# FPV_GROUND_STATION_SOURCE_FILE_PCB.net
KiCad netlist of a schematic drawn in EasyEDA Pro
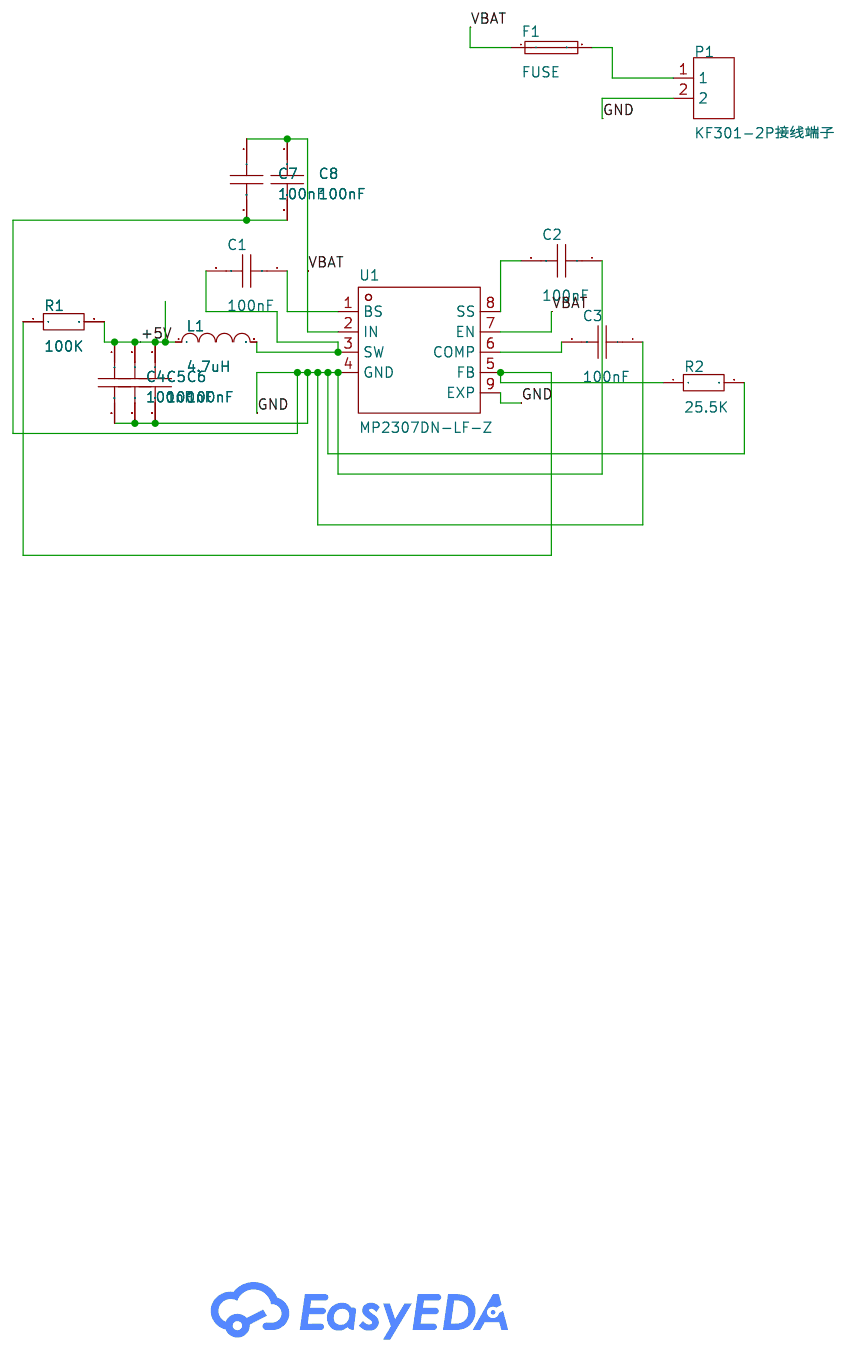
[diagram p0: POWER_BLK]
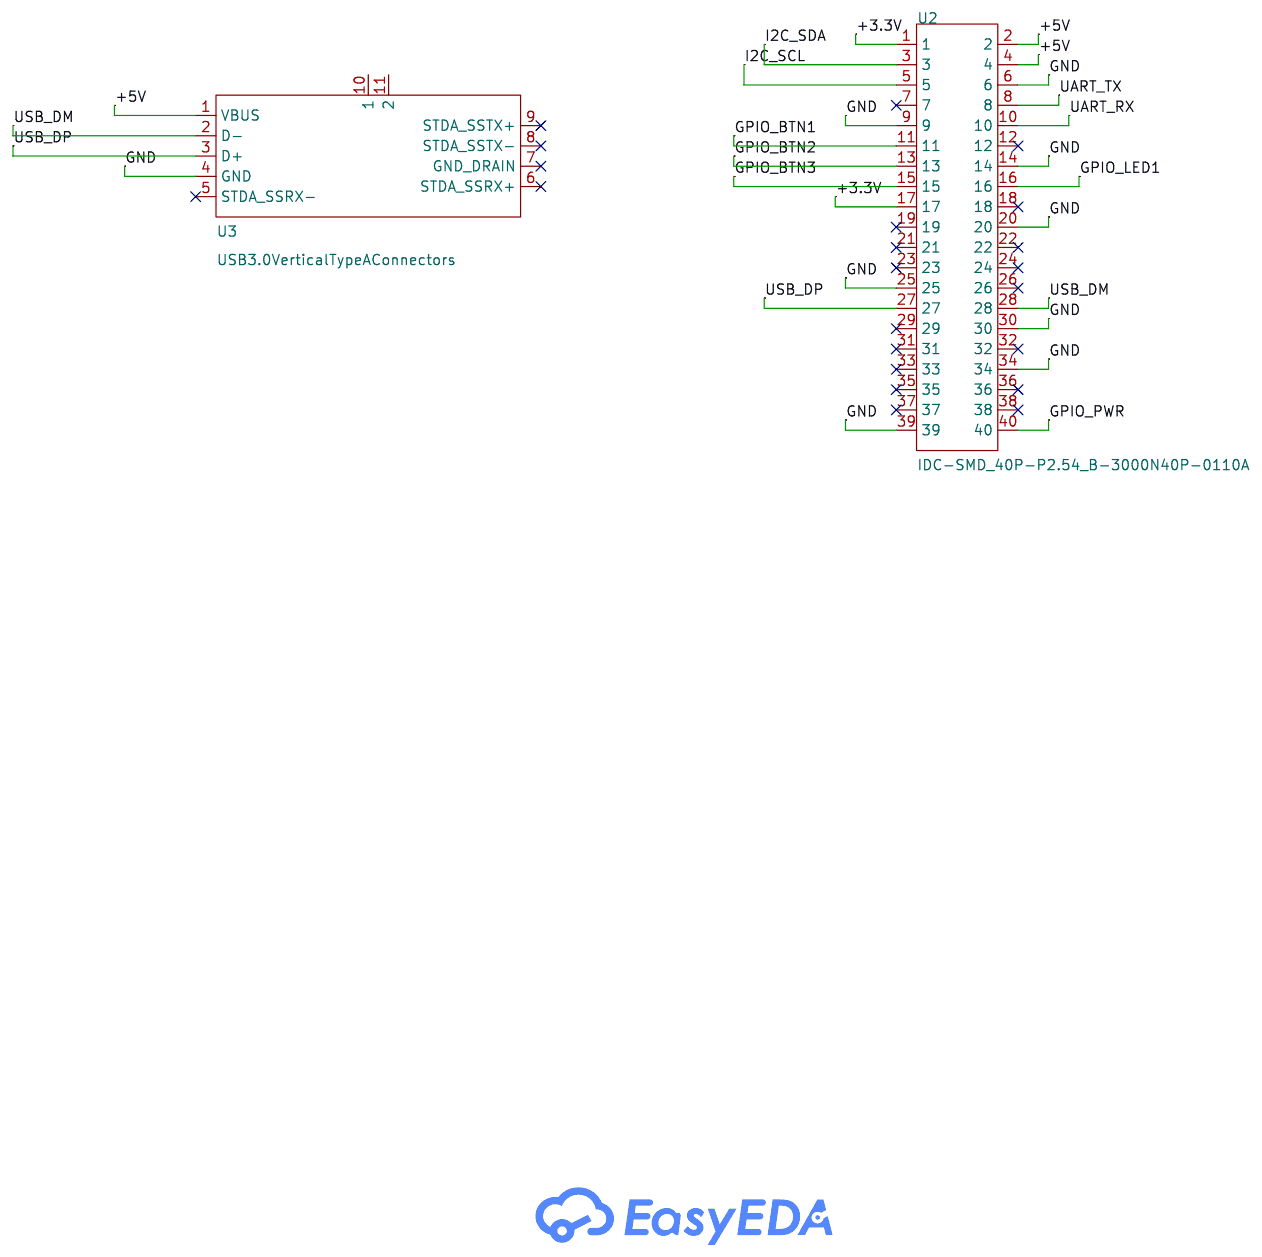
[diagram p1: GPIO header + USB-A]
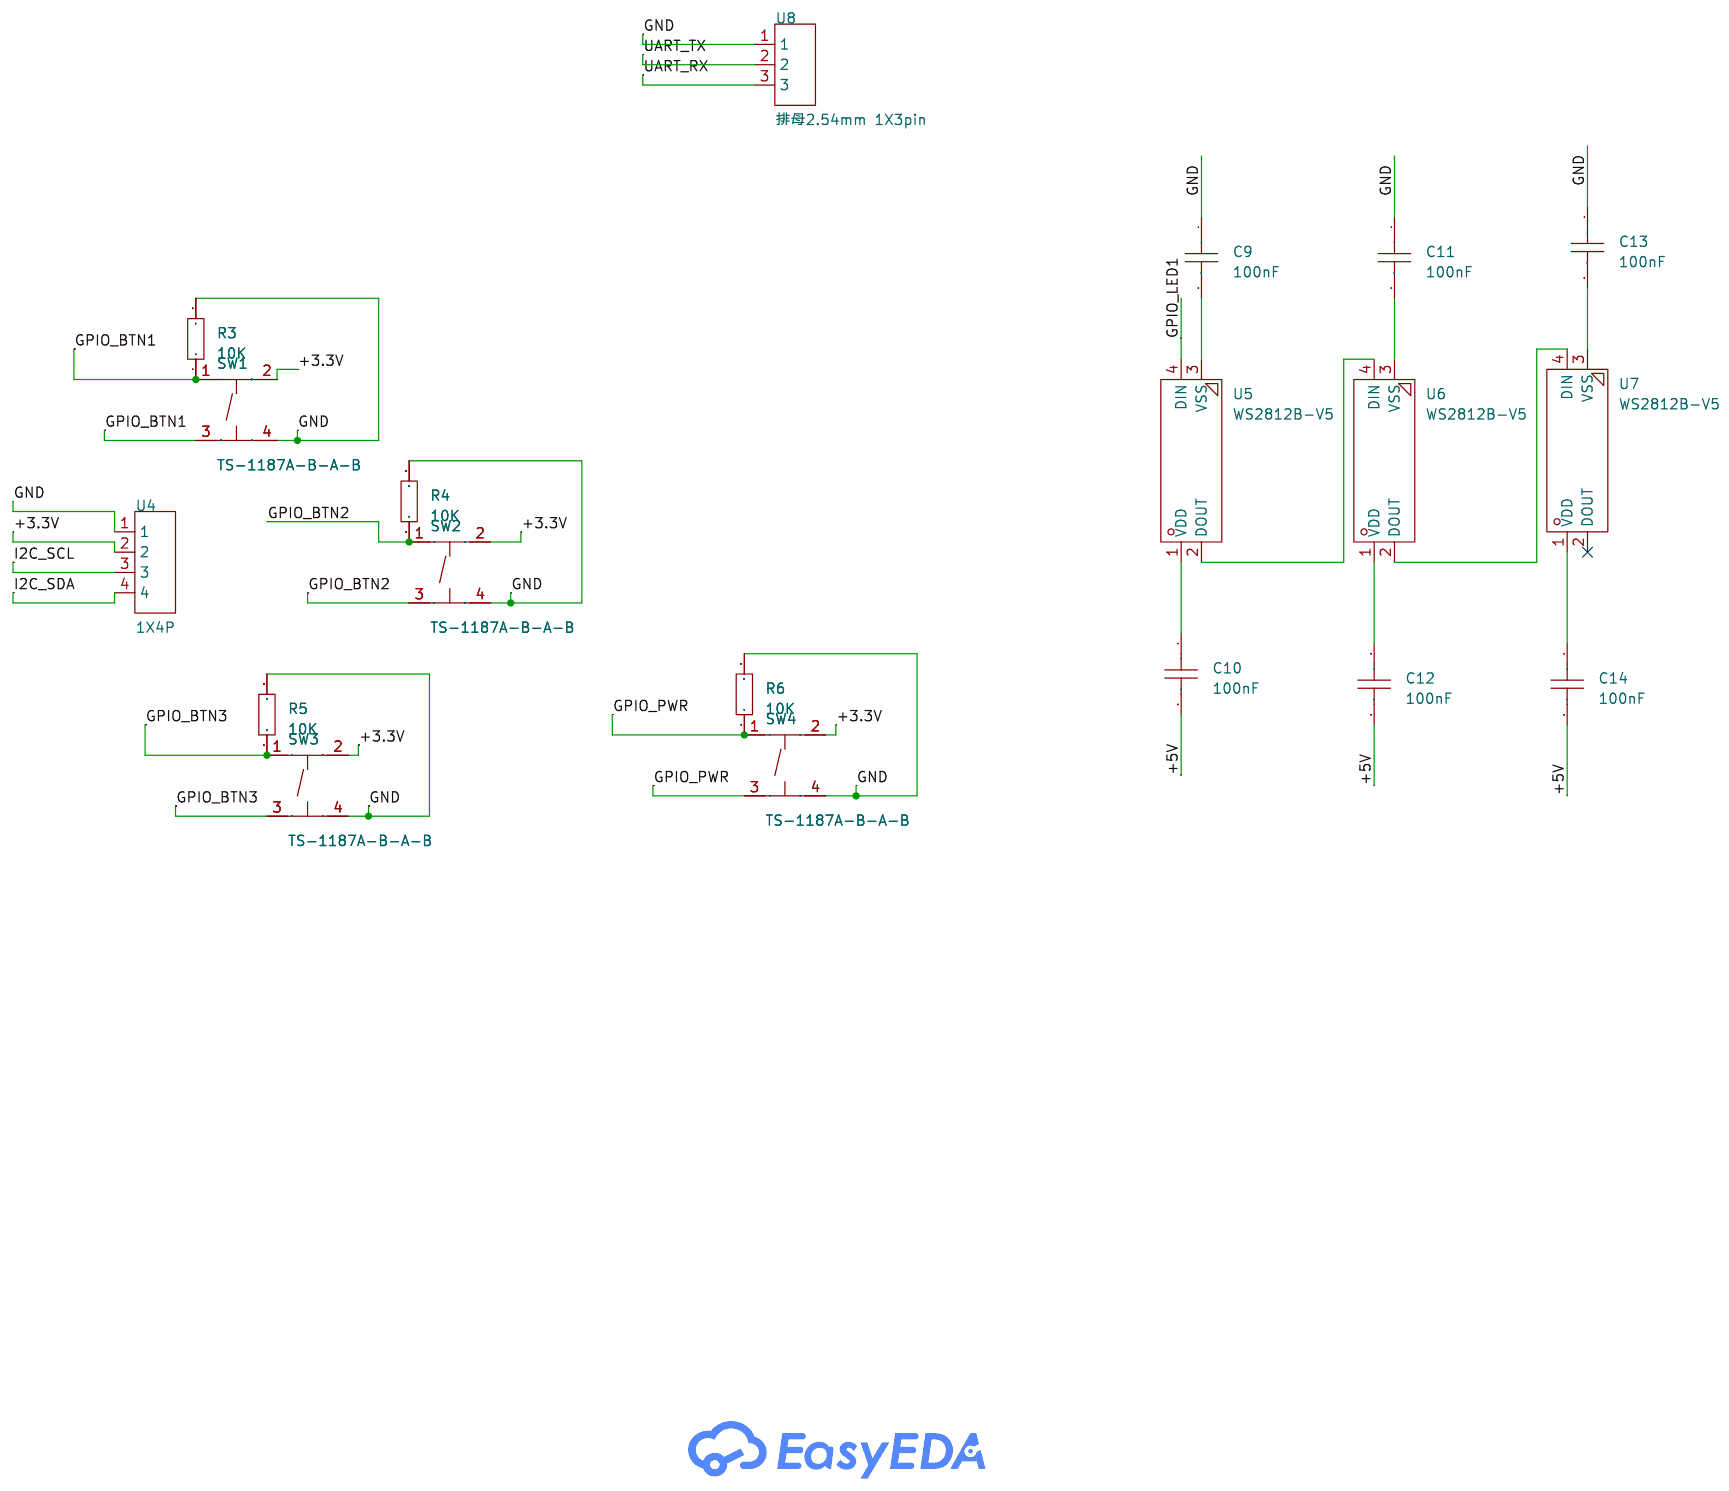
[diagram p2: LEDS AND OLED DISP]

(export (version "E")
  (design (tool "Eeschema 10.0.6"))
  (components
    (comp (ref "C1")
      (value "100nF")
      (footprint "easyedapro:C0603")
      (libsource (lib "easyedapro") (part "CAP"))
    )
    (comp (ref "C2")
      (value "100nF")
      (footprint "easyedapro:C0603")
      (libsource (lib "easyedapro") (part "CAP"))
    )
    (comp (ref "C3")
      (value "100nF")
      (footprint "easyedapro:C0603")
      (libsource (lib "easyedapro") (part "CAP"))
    )
    (comp (ref "C4")
      (value "100nF")
      (footprint "easyedapro:C0603")
      (libsource (lib "easyedapro") (part "CAP"))
    )
    (comp (ref "C5")
      (value "100nF")
      (footprint "easyedapro:C0603")
      (libsource (lib "easyedapro") (part "CAP"))
    )
    (comp (ref "C6")
      (value "100nF")
      (footprint "easyedapro:C0603")
      (libsource (lib "easyedapro") (part "CAP"))
    )
    (comp (ref "C7")
      (value "100nF")
      (footprint "easyedapro:C0603")
      (libsource (lib "easyedapro") (part "CAP"))
    )
    (comp (ref "C8")
      (value "100nF")
      (footprint "easyedapro:C0603")
      (libsource (lib "easyedapro") (part "CAP"))
    )
    (comp (ref "F1")
      (value "FUSE")
      (footprint "easyedapro:F1206")
      (libsource (lib "easyedapro") (part "FUSE"))
    )
    (comp (ref "L1")
      (value "4.7uH")
      (footprint "easyedapro:L0603")
      (libsource (lib "easyedapro") (part "电感"))
    )
    (comp (ref "P1")
      (value "KF301-2P接线端子")
      (footprint "easyedapro:CONN-TH_XY301V-A-5.0-2P")
      (libsource (lib "easyedapro") (part "KF301-2P接线端子"))
    )
    (comp (ref "R1")
      (value "100K")
      (footprint "easyedapro:R0603")
      (libsource (lib "easyedapro") (part "Res"))
    )
    (comp (ref "R2")
      (value "25.5K")
      (footprint "easyedapro:R0603")
      (libsource (lib "easyedapro") (part "Res"))
    )
    (comp (ref "U1")
      (value "MP2307DN-LF-Z")
      (footprint "easyedapro:SOP-8_L4.9-W3.9-P1.27-LS6.0-BL-EP")
      (fields (field (name "Manufacturer") "MPS(芯源)"))
      (libsource (lib "easyedapro") (part "MP2307DN-LF-Z"))
    )
    (comp (ref "U2")
      (value "IDC-SMD_40P-P2.54_B-3000N40P-0110A")
      (footprint "easyedapro:HDR-SMD_40P-P2.54-V-F-R2-C20-LS7.9")
      (libsource (lib "easyedapro") (part "IDC-SMD_40P-P2.54_B-3000N40P-0110A"))
    )
    (comp (ref "U3")
      (value "USB3.0VerticalTypeAConnectors")
      (footprint "easyedapro:USB-A-TH_C9900010398")
      (libsource (lib "easyedapro") (part "USB3.0VERTICALTYPEACONNECTORS"))
    )
    (comp (ref "C9")
      (value "100nF")
      (footprint "easyedapro:C0603")
      (libsource (lib "easyedapro") (part "CAP"))
    )
    (comp (ref "C10")
      (value "100nF")
      (footprint "easyedapro:C0603")
      (libsource (lib "easyedapro") (part "CAP"))
    )
    (comp (ref "C11")
      (value "100nF")
      (footprint "easyedapro:C0603")
      (libsource (lib "easyedapro") (part "CAP"))
    )
    (comp (ref "C12")
      (value "100nF")
      (footprint "easyedapro:C0603")
      (libsource (lib "easyedapro") (part "CAP"))
    )
    (comp (ref "C13")
      (value "100nF")
      (footprint "easyedapro:C0603")
      (libsource (lib "easyedapro") (part "CAP"))
    )
    (comp (ref "C14")
      (value "100nF")
      (footprint "easyedapro:C0603")
      (libsource (lib "easyedapro") (part "CAP"))
    )
    (comp (ref "R3") (value "10K") (footprint "easyedapro:R0603") (libsource (lib "easyedapro") (part "Res")))
    (comp (ref "R4") (value "10K") (footprint "easyedapro:R0603") (libsource (lib "easyedapro") (part "Res")))
    (comp (ref "R5") (value "10K") (footprint "easyedapro:R0603") (libsource (lib "easyedapro") (part "Res")))
    (comp (ref "R6") (value "10K") (footprint "easyedapro:R0603") (libsource (lib "easyedapro") (part "Res")))
    (comp (ref "SW1")
      (value "TS-1187A-B-A-B")
      (footprint "easyedapro:SW-SMD_4P-L5.1-W5.1-P3.70-LS6.5-TL_H1.5")
      (fields (field (name "Manufacturer") "XKB Connection(中国星坤)"))
      (libsource (lib "easyedapro") (part "TS-1187A-B-A-B"))
    )
    (comp (ref "SW2")
      (value "TS-1187A-B-A-B")
      (footprint "easyedapro:SW-SMD_4P-L5.1-W5.1-P3.70-LS6.5-TL_H1.5")
      (fields (field (name "Manufacturer") "XKB Connection(中国星坤)"))
      (libsource (lib "easyedapro") (part "TS-1187A-B-A-B"))
    )
    (comp (ref "SW3")
      (value "TS-1187A-B-A-B")
      (footprint "easyedapro:SW-SMD_4P-L5.1-W5.1-P3.70-LS6.5-TL_H1.5")
      (fields (field (name "Manufacturer") "XKB Connection(中国星坤)"))
      (libsource (lib "easyedapro") (part "TS-1187A-B-A-B"))
    )
    (comp (ref "SW4")
      (value "TS-1187A-B-A-B")
      (footprint "easyedapro:SW-SMD_4P-L5.1-W5.1-P3.70-LS6.5-TL_H1.5")
      (fields (field (name "Manufacturer") "XKB Connection(中国星坤)"))
      (libsource (lib "easyedapro") (part "TS-1187A-B-A-B"))
    )
    (comp (ref "U4")
      (value "1X4P")
      (footprint "easyedapro:CONN-TH_4P-P2.54_C9900022166")
      (libsource (lib "easyedapro") (part "1X4P"))
    )
    (comp (ref "U5")
      (value "WS2812B-V5")
      (footprint "easyedapro:LED-SMD_4P-L5.0-W5.0-TL_WS2812B-B")
      (libsource (lib "easyedapro") (part "WS2812B-V5"))
    )
    (comp (ref "U6")
      (value "WS2812B-V5")
      (footprint "easyedapro:LED-SMD_4P-L5.0-W5.0-TL_WS2812B-B")
      (libsource (lib "easyedapro") (part "WS2812B-V5"))
    )
    (comp (ref "U7")
      (value "WS2812B-V5")
      (footprint "easyedapro:LED-SMD_4P-L5.0-W5.0-TL_WS2812B-B")
      (libsource (lib "easyedapro") (part "WS2812B-V5"))
    )
    (comp (ref "U8")
      (value "排母2.54mm 1X3pin")
      (footprint "easyedapro:HDR-TH_3P-P2.54_CS-1165SDIG")
      (libsource (lib "easyedapro") (part "排母2.54MM 1X3PIN"))
    )
  )
  (nets
    (net (code "1") (name "+3.3V") (class "Default")
      (node (ref "SW1") (pin "2") (pinfunction "B_2") (pintype "unspecified"))
      (node (ref "SW2") (pin "2") (pinfunction "B_2") (pintype "unspecified"))
      (node (ref "SW3") (pin "2") (pinfunction "B_2") (pintype "unspecified"))
      (node (ref "SW4") (pin "2") (pinfunction "B_2") (pintype "unspecified"))
      (node (ref "U2") (pin "1") (pinfunction "1_1") (pintype "unspecified"))
      (node (ref "U2") (pin "17") (pinfunction "17_17") (pintype "unspecified"))
      (node (ref "U4") (pin "2") (pinfunction "2_2") (pintype "unspecified"))
    )
    (net (code "2") (name "+5V") (class "Default")
      (node (ref "C10") (pin "2") (pinfunction "2_2") (pintype "input"))
      (node (ref "C12") (pin "2") (pinfunction "2_2") (pintype "input"))
      (node (ref "C14") (pin "2") (pinfunction "2_2") (pintype "input"))
      (node (ref "C4") (pin "1") (pinfunction "1_1") (pintype "input"))
      (node (ref "C5") (pin "1") (pinfunction "1_1") (pintype "input"))
      (node (ref "C6") (pin "1") (pinfunction "1_1") (pintype "input"))
      (node (ref "L1") (pin "1") (pinfunction "1_1") (pintype "input"))
      (node (ref "R1") (pin "2") (pinfunction "2_2") (pintype "input"))
      (node (ref "U2") (pin "2") (pinfunction "2_2") (pintype "unspecified"))
      (node (ref "U2") (pin "4") (pinfunction "4_4") (pintype "unspecified"))
      (node (ref "U3") (pin "1") (pinfunction "VBUS_1") (pintype "unspecified"))
    )
    (net (code "3") (name "GND") (class "Default")
      (node (ref "C11") (pin "1") (pinfunction "1_1") (pintype "input"))
      (node (ref "C13") (pin "1") (pinfunction "1_1") (pintype "input"))
      (node (ref "C2") (pin "1") (pinfunction "1_1") (pintype "input"))
      (node (ref "C3") (pin "1") (pinfunction "1_1") (pintype "input"))
      (node (ref "C4") (pin "2") (pinfunction "2_2") (pintype "input"))
      (node (ref "C5") (pin "2") (pinfunction "2_2") (pintype "input"))
      (node (ref "C6") (pin "2") (pinfunction "2_2") (pintype "input"))
      (node (ref "C7") (pin "2") (pinfunction "2_2") (pintype "input"))
      (node (ref "C8") (pin "2") (pinfunction "2_2") (pintype "input"))
      (node (ref "C9") (pin "1") (pinfunction "1_1") (pintype "input"))
      (node (ref "P1") (pin "2") (pinfunction "2_2") (pintype "unspecified"))
      (node (ref "R2") (pin "2") (pinfunction "2_2") (pintype "input"))
      (node (ref "R3") (pin "2") (pinfunction "2_2") (pintype "input"))
      (node (ref "R4") (pin "2") (pinfunction "2_2") (pintype "input"))
      (node (ref "R5") (pin "2") (pinfunction "2_2") (pintype "input"))
      (node (ref "R6") (pin "2") (pinfunction "2_2") (pintype "input"))
      (node (ref "SW1") (pin "4") (pinfunction "D_4") (pintype "unspecified"))
      (node (ref "SW2") (pin "4") (pinfunction "D_4") (pintype "unspecified"))
      (node (ref "SW3") (pin "4") (pinfunction "D_4") (pintype "unspecified"))
      (node (ref "SW4") (pin "4") (pinfunction "D_4") (pintype "unspecified"))
      (node (ref "U1") (pin "4") (pinfunction "GND_4") (pintype "unspecified"))
      (node (ref "U1") (pin "9") (pinfunction "EXP_9") (pintype "unspecified"))
      (node (ref "U2") (pin "14") (pinfunction "14_14") (pintype "unspecified"))
      (node (ref "U2") (pin "20") (pinfunction "20_20") (pintype "unspecified"))
      (node (ref "U2") (pin "25") (pinfunction "25_25") (pintype "unspecified"))
      (node (ref "U2") (pin "30") (pinfunction "30_30") (pintype "unspecified"))
      (node (ref "U2") (pin "34") (pinfunction "34_34") (pintype "unspecified"))
      (node (ref "U2") (pin "39") (pinfunction "39_39") (pintype "unspecified"))
      (node (ref "U2") (pin "6") (pinfunction "6_6") (pintype "unspecified"))
      (node (ref "U2") (pin "9") (pinfunction "9_9") (pintype "unspecified"))
      (node (ref "U3") (pin "4") (pinfunction "GND_4") (pintype "unspecified"))
      (node (ref "U4") (pin "1") (pinfunction "1_1") (pintype "unspecified"))
      (node (ref "U8") (pin "1") (pinfunction "1_1") (pintype "unspecified"))
    )
    (net (code "4") (name "GPIO_BTN1") (class "Default")
      (node (ref "R3") (pin "1") (pinfunction "1_1") (pintype "input"))
      (node (ref "SW1") (pin "1") (pinfunction "A_1") (pintype "unspecified"))
      (node (ref "SW1") (pin "3") (pinfunction "C_3") (pintype "unspecified"))
      (node (ref "U2") (pin "11") (pinfunction "11_11") (pintype "unspecified"))
    )
    (net (code "5") (name "GPIO_BTN2") (class "Default")
      (node (ref "R4") (pin "1") (pinfunction "1_1") (pintype "input"))
      (node (ref "SW2") (pin "1") (pinfunction "A_1") (pintype "unspecified"))
      (node (ref "SW2") (pin "3") (pinfunction "C_3") (pintype "unspecified"))
      (node (ref "U2") (pin "13") (pinfunction "13_13") (pintype "unspecified"))
    )
    (net (code "6") (name "GPIO_BTN3") (class "Default")
      (node (ref "R5") (pin "1") (pinfunction "1_1") (pintype "input"))
      (node (ref "SW3") (pin "1") (pinfunction "A_1") (pintype "unspecified"))
      (node (ref "SW3") (pin "3") (pinfunction "C_3") (pintype "unspecified"))
      (node (ref "U2") (pin "15") (pinfunction "15_15") (pintype "unspecified"))
    )
    (net (code "7") (name "GPIO_LED1") (class "Default")
      (node (ref "U2") (pin "16") (pinfunction "16_16") (pintype "unspecified"))
      (node (ref "U5") (pin "4") (pinfunction "DIN_4") (pintype "unspecified"))
    )
    (net (code "8") (name "GPIO_PWR") (class "Default")
      (node (ref "R6") (pin "1") (pinfunction "1_1") (pintype "input"))
      (node (ref "SW4") (pin "1") (pinfunction "A_1") (pintype "unspecified"))
      (node (ref "SW4") (pin "3") (pinfunction "C_3") (pintype "unspecified"))
      (node (ref "U2") (pin "40") (pinfunction "40_40") (pintype "unspecified"))
    )
    (net (code "9") (name "I2C_SCL") (class "Default")
      (node (ref "U2") (pin "5") (pinfunction "5_5") (pintype "unspecified"))
      (node (ref "U4") (pin "3") (pinfunction "3_3") (pintype "unspecified"))
    )
    (net (code "10") (name "I2C_SDA") (class "Default")
      (node (ref "U2") (pin "3") (pinfunction "3_3") (pintype "unspecified"))
      (node (ref "U4") (pin "4") (pinfunction "4_4") (pintype "unspecified"))
    )
    (net (code "11") (name "Net-(F1-Pad2)") (class "Default")
      (node (ref "F1") (pin "2") (pinfunction "2_2") (pintype "unspecified"))
      (node (ref "P1") (pin "1") (pinfunction "1_1") (pintype "unspecified"))
    )
    (net (code "12") (name "Net-(U1-BS)") (class "Default")
      (node (ref "C1") (pin "1") (pinfunction "1_1") (pintype "input"))
      (node (ref "U1") (pin "1") (pinfunction "BS_1") (pintype "unspecified"))
    )
    (net (code "13") (name "Net-(U1-COMP)") (class "Default")
      (node (ref "C3") (pin "2") (pinfunction "2_2") (pintype "input"))
      (node (ref "U1") (pin "6") (pinfunction "COMP_6") (pintype "unspecified"))
    )
    (net (code "14") (name "Net-(U1-FB)") (class "Default")
      (node (ref "R1") (pin "1") (pinfunction "1_1") (pintype "input"))
      (node (ref "R2") (pin "1") (pinfunction "1_1") (pintype "input"))
      (node (ref "U1") (pin "5") (pinfunction "FB_5") (pintype "unspecified"))
    )
    (net (code "15") (name "Net-(U1-SS)") (class "Default")
      (node (ref "C2") (pin "2") (pinfunction "2_2") (pintype "input"))
      (node (ref "U1") (pin "8") (pinfunction "SS_8") (pintype "unspecified"))
    )
    (net (code "16") (name "Net-(U1-SW)") (class "Default")
      (node (ref "C1") (pin "2") (pinfunction "2_2") (pintype "input"))
      (node (ref "L1") (pin "2") (pinfunction "2_2") (pintype "input"))
      (node (ref "U1") (pin "3") (pinfunction "SW_3") (pintype "unspecified"))
    )
    (net (code "17") (name "Net-(U5-DOUT)") (class "Default")
      (node (ref "U5") (pin "2") (pinfunction "DOUT_2") (pintype "unspecified"))
      (node (ref "U6") (pin "4") (pinfunction "DIN_4") (pintype "unspecified"))
    )
    (net (code "18") (name "Net-(U5-VDD)") (class "Default")
      (node (ref "C10") (pin "1") (pinfunction "1_1") (pintype "input"))
      (node (ref "U5") (pin "1") (pinfunction "VDD_1") (pintype "unspecified"))
    )
    (net (code "19") (name "Net-(U5-VSS)") (class "Default")
      (node (ref "C9") (pin "2") (pinfunction "2_2") (pintype "input"))
      (node (ref "U5") (pin "3") (pinfunction "VSS_3") (pintype "unspecified"))
    )
    (net (code "20") (name "Net-(U6-DOUT)") (class "Default")
      (node (ref "U6") (pin "2") (pinfunction "DOUT_2") (pintype "unspecified"))
      (node (ref "U7") (pin "4") (pinfunction "DIN_4") (pintype "unspecified"))
    )
    (net (code "21") (name "Net-(U6-VDD)") (class "Default")
      (node (ref "C12") (pin "1") (pinfunction "1_1") (pintype "input"))
      (node (ref "U6") (pin "1") (pinfunction "VDD_1") (pintype "unspecified"))
    )
    (net (code "22") (name "Net-(U6-VSS)") (class "Default")
      (node (ref "C11") (pin "2") (pinfunction "2_2") (pintype "input"))
      (node (ref "U6") (pin "3") (pinfunction "VSS_3") (pintype "unspecified"))
    )
    (net (code "23") (name "Net-(U7-VDD)") (class "Default")
      (node (ref "C14") (pin "1") (pinfunction "1_1") (pintype "input"))
      (node (ref "U7") (pin "1") (pinfunction "VDD_1") (pintype "unspecified"))
    )
    (net (code "24") (name "Net-(U7-VSS)") (class "Default")
      (node (ref "C13") (pin "2") (pinfunction "2_2") (pintype "input"))
      (node (ref "U7") (pin "3") (pinfunction "VSS_3") (pintype "unspecified"))
    )
    (net (code "25") (name "UART_RX") (class "Default")
      (node (ref "U2") (pin "10") (pinfunction "10_10") (pintype "unspecified"))
      (node (ref "U8") (pin "3") (pinfunction "3_3") (pintype "unspecified"))
    )
    (net (code "26") (name "UART_TX") (class "Default")
      (node (ref "U2") (pin "8") (pinfunction "8_8") (pintype "unspecified"))
      (node (ref "U8") (pin "2") (pinfunction "2_2") (pintype "unspecified"))
    )
    (net (code "27") (name "USB_DM") (class "Default")
      (node (ref "U2") (pin "28") (pinfunction "28_28") (pintype "unspecified"))
      (node (ref "U3") (pin "2") (pinfunction "D-_2") (pintype "unspecified"))
    )
    (net (code "28") (name "USB_DP") (class "Default")
      (node (ref "U2") (pin "27") (pinfunction "27_27") (pintype "unspecified"))
      (node (ref "U3") (pin "3") (pinfunction "D+_3") (pintype "unspecified"))
    )
    (net (code "29") (name "VBAT") (class "Default")
      (node (ref "C7") (pin "1") (pinfunction "1_1") (pintype "input"))
      (node (ref "C8") (pin "1") (pinfunction "1_1") (pintype "input"))
      (node (ref "F1") (pin "1") (pinfunction "1_1") (pintype "unspecified"))
      (node (ref "U1") (pin "2") (pinfunction "IN_2") (pintype "unspecified"))
      (node (ref "U1") (pin "7") (pinfunction "EN_7") (pintype "unspecified"))
    )
    (net (code "30") (name "unconnected-(U2-Pad7)") (class "Default")
      (node (ref "U2") (pin "7") (pinfunction "7_7") (pintype "unspecified+no_connect"))
    )
    (net (code "31") (name "unconnected-(U2-Pad12)") (class "Default")
      (node (ref "U2") (pin "12") (pinfunction "12_12") (pintype "unspecified+no_connect"))
    )
    (net (code "32") (name "unconnected-(U2-Pad18)") (class "Default")
      (node (ref "U2") (pin "18") (pinfunction "18_18") (pintype "unspecified+no_connect"))
    )
    (net (code "33") (name "unconnected-(U2-Pad19)") (class "Default")
      (node (ref "U2") (pin "19") (pinfunction "19_19") (pintype "unspecified+no_connect"))
    )
    (net (code "34") (name "unconnected-(U2-Pad21)") (class "Default")
      (node (ref "U2") (pin "21") (pinfunction "21_21") (pintype "unspecified+no_connect"))
    )
    (net (code "35") (name "unconnected-(U2-Pad22)") (class "Default")
      (node (ref "U2") (pin "22") (pinfunction "22_22") (pintype "unspecified+no_connect"))
    )
    (net (code "36") (name "unconnected-(U2-Pad23)") (class "Default")
      (node (ref "U2") (pin "23") (pinfunction "23_23") (pintype "unspecified+no_connect"))
    )
    (net (code "37") (name "unconnected-(U2-Pad24)") (class "Default")
      (node (ref "U2") (pin "24") (pinfunction "24_24") (pintype "unspecified+no_connect"))
    )
    (net (code "38") (name "unconnected-(U2-Pad26)") (class "Default")
      (node (ref "U2") (pin "26") (pinfunction "26_26") (pintype "unspecified+no_connect"))
    )
    (net (code "39") (name "unconnected-(U2-Pad29)") (class "Default")
      (node (ref "U2") (pin "29") (pinfunction "29_29") (pintype "unspecified+no_connect"))
    )
    (net (code "40") (name "unconnected-(U2-Pad31)") (class "Default")
      (node (ref "U2") (pin "31") (pinfunction "31_31") (pintype "unspecified+no_connect"))
    )
    (net (code "41") (name "unconnected-(U2-Pad32)") (class "Default")
      (node (ref "U2") (pin "32") (pinfunction "32_32") (pintype "unspecified+no_connect"))
    )
    (net (code "42") (name "unconnected-(U2-Pad33)") (class "Default")
      (node (ref "U2") (pin "33") (pinfunction "33_33") (pintype "unspecified+no_connect"))
    )
    (net (code "43") (name "unconnected-(U2-Pad35)") (class "Default")
      (node (ref "U2") (pin "35") (pinfunction "35_35") (pintype "unspecified+no_connect"))
    )
    (net (code "44") (name "unconnected-(U2-Pad36)") (class "Default")
      (node (ref "U2") (pin "36") (pinfunction "36_36") (pintype "unspecified+no_connect"))
    )
    (net (code "45") (name "unconnected-(U2-Pad37)") (class "Default")
      (node (ref "U2") (pin "37") (pinfunction "37_37") (pintype "unspecified+no_connect"))
    )
    (net (code "46") (name "unconnected-(U2-Pad38)") (class "Default")
      (node (ref "U2") (pin "38") (pinfunction "38_38") (pintype "unspecified+no_connect"))
    )
    (net (code "47") (name "unconnected-(U3-1-Pad10)") (class "Default")
      (node (ref "U3") (pin "10") (pinfunction "1_10") (pintype "unspecified"))
    )
    (net (code "48") (name "unconnected-(U3-2-Pad11)") (class "Default")
      (node (ref "U3") (pin "11") (pinfunction "2_11") (pintype "unspecified"))
    )
    (net (code "49") (name "unconnected-(U3-GND_DRAIN-Pad7)") (class "Default")
      (node (ref "U3") (pin "7") (pinfunction "GND_DRAIN_7") (pintype "unspecified+no_connect"))
    )
    (net (code "50") (name "unconnected-(U3-STDA_SSRX+-Pad6)") (class "Default")
      (node (ref "U3") (pin "6") (pinfunction "STDA_SSRX+_6") (pintype "unspecified+no_connect"))
    )
    (net (code "51") (name "unconnected-(U3-STDA_SSRX--Pad5)") (class "Default")
      (node (ref "U3") (pin "5") (pinfunction "STDA_SSRX-_5") (pintype "unspecified+no_connect"))
    )
    (net (code "52") (name "unconnected-(U3-STDA_SSTX+-Pad9)") (class "Default")
      (node (ref "U3") (pin "9") (pinfunction "STDA_SSTX+_9") (pintype "unspecified+no_connect"))
    )
    (net (code "53") (name "unconnected-(U3-STDA_SSTX--Pad8)") (class "Default")
      (node (ref "U3") (pin "8") (pinfunction "STDA_SSTX-_8") (pintype "unspecified+no_connect"))
    )
    (net (code "54") (name "unconnected-(U7-DOUT-Pad2)") (class "Default")
      (node (ref "U7") (pin "2") (pinfunction "DOUT_2") (pintype "unspecified+no_connect"))
    )
  )
)
